# Mechanical.net
KiCad netlist of a schematic drawn in Altium Designer
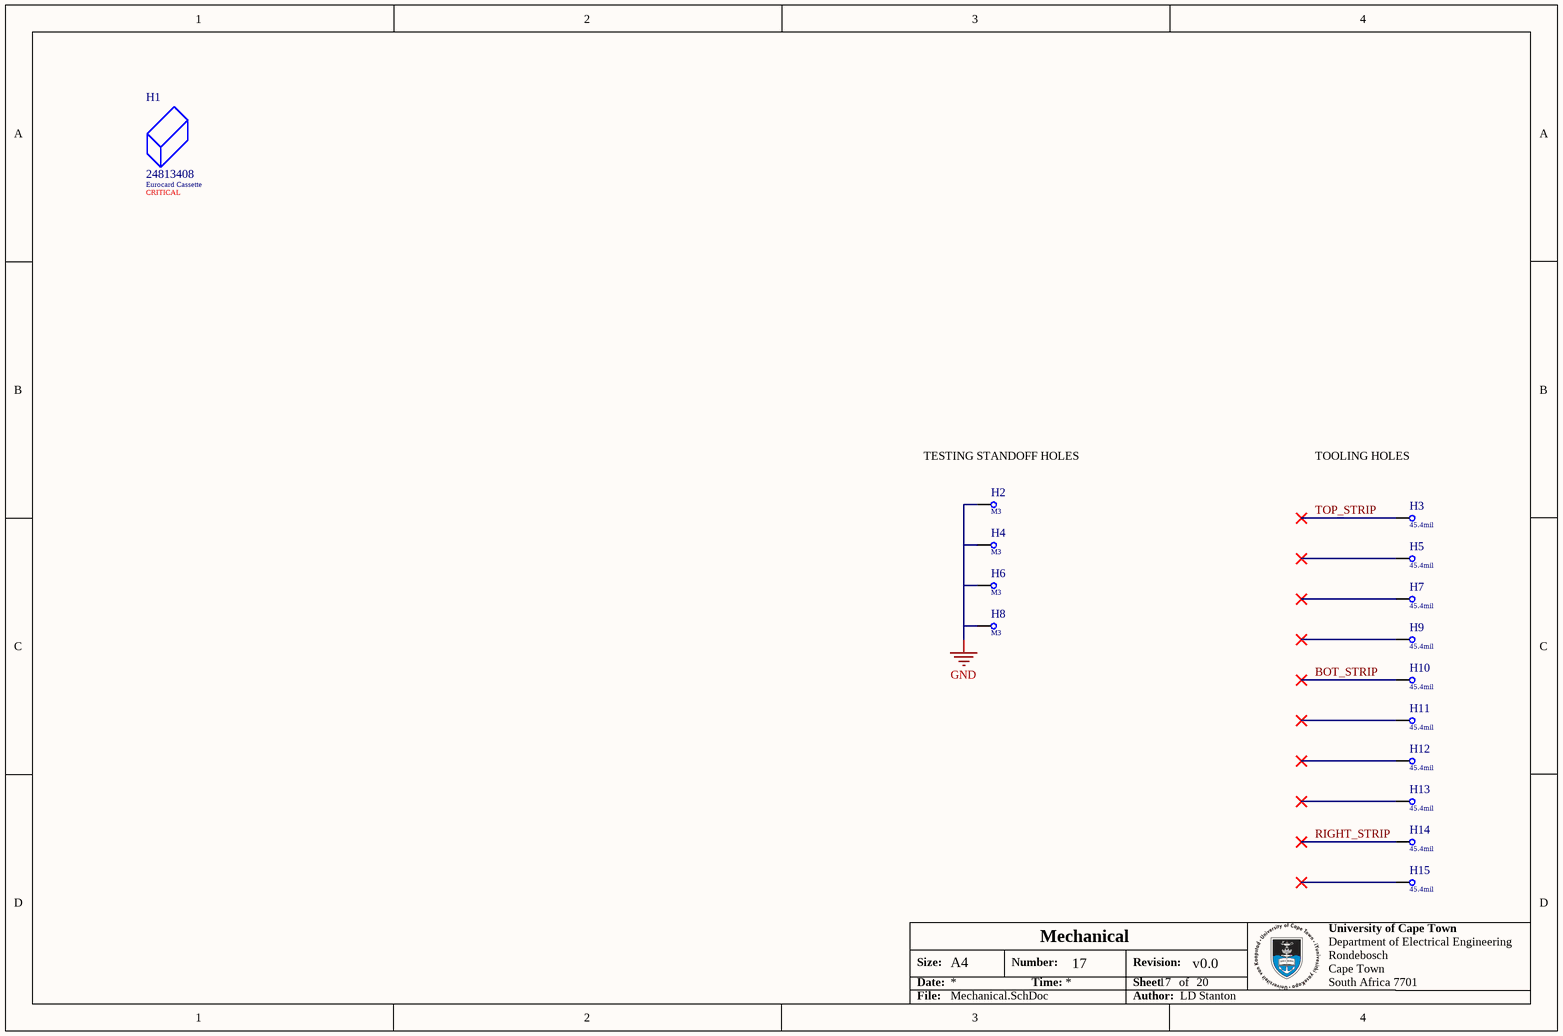
[diagram p0: Mechanical.SchDoc]

(export (version "E")
  (design (tool "Eeschema 10.0.6"))
  (components
    (comp (ref "H1")
      (value "24813408")
      (description "Plug-in unit Pro, 3 HE, 8 TE, 24813-408, Schroff")
      (fields (field (name "TYPE") "Eurocard Cassette") (field (name "PLACEMENT") "CRITICAL"))
      (libsource (lib "University of Cape Town") (part "Box Symbol"))
    )
    (comp (ref "H2")
      (value "Mounting Hole M3")
      (footprint "Mounting Hole M3 Plated Tight Via")
      (description "M3 Mounting Hole")
      (fields (field (name "SIZE") "M3"))
      (libsource (lib "University of Cape Town") (part "Hole"))
    )
    (comp (ref "H3")
      (value "Tooling Hole JLCPCB")
      (footprint "Tooling Hole JLCPCB")
      (description "Tooling Hole Specified by JLCPCB")
      (fields (field (name "SIZE") "45.4mil"))
      (libsource (lib "University of Cape Town") (part "Hole"))
    )
    (comp (ref "H4")
      (value "Mounting Hole M3")
      (footprint "Mounting Hole M3 Plated Tight Via")
      (description "M3 Mounting Hole")
      (fields (field (name "SIZE") "M3"))
      (libsource (lib "University of Cape Town") (part "Hole"))
    )
    (comp (ref "H5")
      (value "Tooling Hole JLCPCB")
      (footprint "Tooling Hole JLCPCB")
      (description "Tooling Hole Specified by JLCPCB")
      (fields (field (name "SIZE") "45.4mil"))
      (libsource (lib "University of Cape Town") (part "Hole"))
    )
    (comp (ref "H6")
      (value "Mounting Hole M3")
      (footprint "Mounting Hole M3 Plated Tight Via")
      (description "M3 Mounting Hole")
      (fields (field (name "SIZE") "M3"))
      (libsource (lib "University of Cape Town") (part "Hole"))
    )
    (comp (ref "H7")
      (value "Tooling Hole JLCPCB")
      (footprint "Tooling Hole JLCPCB")
      (description "Tooling Hole Specified by JLCPCB")
      (fields (field (name "SIZE") "45.4mil"))
      (libsource (lib "University of Cape Town") (part "Hole"))
    )
    (comp (ref "H8")
      (value "Mounting Hole M3")
      (footprint "Mounting Hole M3 Plated Tight Via")
      (description "M3 Mounting Hole")
      (fields (field (name "SIZE") "M3"))
      (libsource (lib "University of Cape Town") (part "Hole"))
    )
    (comp (ref "H9")
      (value "Tooling Hole JLCPCB")
      (footprint "Tooling Hole JLCPCB")
      (description "Tooling Hole Specified by JLCPCB")
      (fields (field (name "SIZE") "45.4mil"))
      (libsource (lib "University of Cape Town") (part "Hole"))
    )
    (comp (ref "H10")
      (value "Tooling Hole JLCPCB")
      (footprint "Tooling Hole JLCPCB")
      (description "Tooling Hole Specified by JLCPCB")
      (fields (field (name "SIZE") "45.4mil"))
      (libsource (lib "University of Cape Town") (part "Hole"))
    )
    (comp (ref "H11")
      (value "Tooling Hole JLCPCB")
      (footprint "Tooling Hole JLCPCB")
      (description "Tooling Hole Specified by JLCPCB")
      (fields (field (name "SIZE") "45.4mil"))
      (libsource (lib "University of Cape Town") (part "Hole"))
    )
    (comp (ref "H12")
      (value "Tooling Hole JLCPCB")
      (footprint "Tooling Hole JLCPCB")
      (description "Tooling Hole Specified by JLCPCB")
      (fields (field (name "SIZE") "45.4mil"))
      (libsource (lib "University of Cape Town") (part "Hole"))
    )
    (comp (ref "H13")
      (value "Tooling Hole JLCPCB")
      (footprint "Tooling Hole JLCPCB")
      (description "Tooling Hole Specified by JLCPCB")
      (fields (field (name "SIZE") "45.4mil"))
      (libsource (lib "University of Cape Town") (part "Hole"))
    )
    (comp (ref "H14")
      (value "Tooling Hole JLCPCB")
      (footprint "Tooling Hole JLCPCB")
      (description "Tooling Hole Specified by JLCPCB")
      (fields (field (name "SIZE") "45.4mil"))
      (libsource (lib "University of Cape Town") (part "Hole"))
    )
    (comp (ref "H15")
      (value "Tooling Hole JLCPCB")
      (footprint "Tooling Hole JLCPCB")
      (description "Tooling Hole Specified by JLCPCB")
      (fields (field (name "SIZE") "45.4mil"))
      (libsource (lib "University of Cape Town") (part "Hole"))
    )
  )
  (nets
    (net (code "1") (name "/BOT_STRIP") (class "Default")
      (node (ref "H10") (pin "1") (pinfunction "1_1") (pintype "passive+no_connect"))
    )
    (net (code "2") (name "/RIGHT_STRIP") (class "Default")
      (node (ref "H14") (pin "1") (pinfunction "1_1") (pintype "passive+no_connect"))
    )
    (net (code "3") (name "/TOP_STRIP") (class "Default")
      (node (ref "H3") (pin "1") (pinfunction "1_1") (pintype "passive+no_connect"))
    )
    (net (code "4") (name "GND") (class "Default")
      (node (ref "H2") (pin "1") (pinfunction "1_1") (pintype "passive"))
      (node (ref "H4") (pin "1") (pinfunction "1_1") (pintype "passive"))
      (node (ref "H6") (pin "1") (pinfunction "1_1") (pintype "passive"))
      (node (ref "H8") (pin "1") (pinfunction "1_1") (pintype "passive"))
    )
    (net (code "5") (name "unconnected-(H5-Pad1)") (class "Default")
      (node (ref "H5") (pin "1") (pinfunction "1_1") (pintype "passive+no_connect"))
    )
    (net (code "6") (name "unconnected-(H7-Pad1)") (class "Default")
      (node (ref "H7") (pin "1") (pinfunction "1_1") (pintype "passive+no_connect"))
    )
    (net (code "7") (name "unconnected-(H9-Pad1)") (class "Default")
      (node (ref "H9") (pin "1") (pinfunction "1_1") (pintype "passive+no_connect"))
    )
    (net (code "8") (name "unconnected-(H11-Pad1)") (class "Default")
      (node (ref "H11") (pin "1") (pinfunction "1_1") (pintype "passive+no_connect"))
    )
    (net (code "9") (name "unconnected-(H12-Pad1)") (class "Default")
      (node (ref "H12") (pin "1") (pinfunction "1_1") (pintype "passive+no_connect"))
    )
    (net (code "10") (name "unconnected-(H13-Pad1)") (class "Default")
      (node (ref "H13") (pin "1") (pinfunction "1_1") (pintype "passive+no_connect"))
    )
    (net (code "11") (name "unconnected-(H15-Pad1)") (class "Default")
      (node (ref "H15") (pin "1") (pinfunction "1_1") (pintype "passive+no_connect"))
    )
  )
)
